# 12_-_RTC.net
KiCad netlist of a schematic drawn in Altium Designer
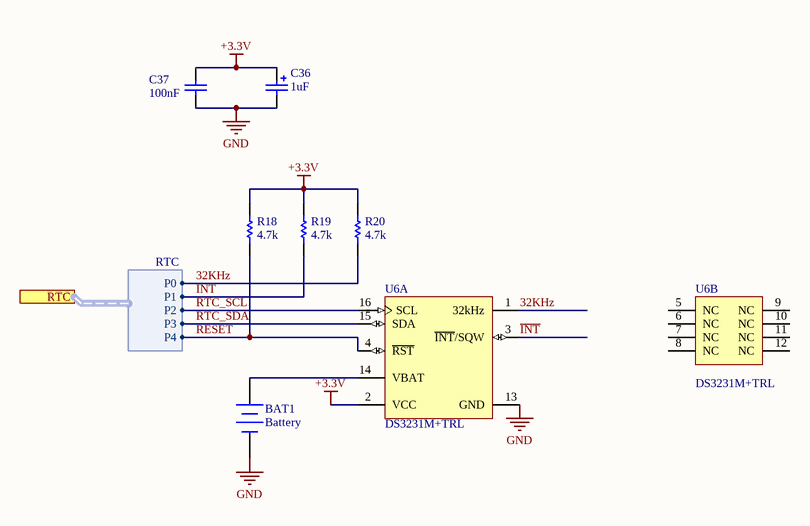
[diagram p0: [12] - RTC.SchDoc]

(export (version "E")
  (design (tool "Eeschema 10.0.6"))
  (components
    (comp (ref "BAT1")
      (value "Battery")
      (footprint "Bat")
      (description "Multicell Battery")
      (fields (field (name "PUBLISHER") "Altium Limited"))
      (libsource (lib "Miscellaneous Devices") (part "Battery"))
    )
    (comp (ref "C36")
      (value "Capacitor Polarized")
      (footprint "Tantalum 3216 A")
      (description "Aluminium SMD Capacitors")
      (fields
        (field (name "MANUFACTURER") "Panasonic")
        (field (name "MANUFACTURER PART NUMBER") "EEE-1VA331P")
        (field (name "CAPACITANCE") "1uF")
      )
      (libsource (lib "Altium_Library") (part "Capacitor Polarized"))
    )
    (comp (ref "C37")
      (value "Capacitor")
      (footprint "Cap 0603")
      (description "Chip Capacitor Nonpolar")
      (fields
        (field (name "MANUFACTURER") "Samsung")
        (field (name "MANUFACTURER PART NUMBER") "CL10B104KB8NNNC")
        (field (name "CAPACITANCE") "100nF")
      )
      (libsource (lib "Altium_Library") (part "Capacitor"))
    )
    (comp (ref "R18")
      (value "Res1")
      (footprint "Res-0603")
      (description "Chip Resistor")
      (fields
        (field (name "MANUFACTURER") "Panasonic")
        (field (name "MANUFACTURER PART NUMBER") "ERJ-3GEYJ222V")
        (field (name "RESISTANCE") "4.7k")
      )
      (libsource (lib "Altium_Library") (part "Res1"))
    )
    (comp (ref "R19")
      (value "Res1")
      (footprint "Res-0603")
      (description "Chip Resistor")
      (fields
        (field (name "MANUFACTURER") "Panasonic")
        (field (name "MANUFACTURER PART NUMBER") "ERJ-3GEYJ222V")
        (field (name "RESISTANCE") "4.7k")
      )
      (libsource (lib "Altium_Library") (part "Res1"))
    )
    (comp (ref "R20")
      (value "Res1")
      (footprint "Res-0603")
      (description "Chip Resistor")
      (fields
        (field (name "MANUFACTURER") "Panasonic")
        (field (name "MANUFACTURER PART NUMBER") "ERJ-3GEYJ222V")
        (field (name "RESISTANCE") "4.7k")
      )
      (libsource (lib "Altium_Library") (part "Res1"))
    )
    (comp (ref "U6")
      (value "DS3231M+TRL")
      (footprint "W16MK+1_N")
      (description "+/-5ppm, MEMS based Real-Time Clock, I2C Interface, 16-Pin SO, -40 to 85 degC, Pb-Free, Reel")
      (libsource (lib "Altium Content Vault") (part "PR-RTC-DS3231M-IL16"))
    )
  )
  (nets
    (net (code "2") (name "+3.3V") (class "Default")
      (node (ref "C36") (pin "1") (pinfunction "1_1") (pintype "passive"))
      (node (ref "C37") (pin "2") (pinfunction "2_2") (pintype "passive"))
      (node (ref "R18") (pin "1") (pinfunction "1_1") (pintype "passive"))
      (node (ref "R19") (pin "1") (pinfunction "1_1") (pintype "passive"))
      (node (ref "R20") (pin "1") (pinfunction "1_1") (pintype "passive"))
      (node (ref "U6") (pin "2") (pinfunction "VCC_2") (pintype "power_in"))
    )
    (net (code "3") (name "/32KHz") (class "Default")
      (node (ref "R20") (pin "2") (pinfunction "2_2") (pintype "passive"))
      (node (ref "U6") (pin "1") (pinfunction "32kHz_1") (pintype "open_collector"))
    )
    (net (code "4") (name "/RESET") (class "Default")
      (node (ref "R18") (pin "2") (pinfunction "2_2") (pintype "passive"))
      (node (ref "U6") (pin "4") (pinfunction "~{RST}_4") (pintype "bidirectional"))
    )
    (net (code "5") (name "/RTC_SCL") (class "Default")
      (node (ref "U6") (pin "16") (pinfunction "SCL_16") (pintype "input"))
    )
    (net (code "6") (name "/RTC_SDA") (class "Default")
      (node (ref "U6") (pin "15") (pinfunction "SDA_15") (pintype "bidirectional"))
    )
    (net (code "8") (name "/~{INT}") (class "Default")
      (node (ref "R19") (pin "2") (pinfunction "2_2") (pintype "passive"))
      (node (ref "U6") (pin "3") (pinfunction "~{INT}/SQW_3") (pintype "bidirectional"))
    )
    (net (code "9") (name "GND") (class "Default")
      (node (ref "BAT1") (pin "2") (pinfunction "-_2") (pintype "passive"))
      (node (ref "C36") (pin "2") (pinfunction "2_2") (pintype "passive"))
      (node (ref "C37") (pin "1") (pinfunction "1_1") (pintype "passive"))
      (node (ref "U6") (pin "13") (pinfunction "GND_13") (pintype "power_in"))
    )
    (net (code "10") (name "Net-(BAT1-+)") (class "Default")
      (node (ref "BAT1") (pin "1") (pinfunction "+_1") (pintype "passive"))
      (node (ref "U6") (pin "14") (pinfunction "VBAT_14") (pintype "power_in"))
    )
    (net (code "11") (name "unconnected-(U6B-NC-Pad5)") (class "Default")
      (node (ref "U6") (pin "5") (pinfunction "NC_5") (pintype "passive"))
    )
    (net (code "12") (name "unconnected-(U6B-NC-Pad6)") (class "Default")
      (node (ref "U6") (pin "6") (pinfunction "NC_6") (pintype "passive"))
    )
    (net (code "13") (name "unconnected-(U6B-NC-Pad7)") (class "Default")
      (node (ref "U6") (pin "7") (pinfunction "NC_7") (pintype "passive"))
    )
    (net (code "14") (name "unconnected-(U6B-NC-Pad8)") (class "Default")
      (node (ref "U6") (pin "8") (pinfunction "NC_8") (pintype "passive"))
    )
    (net (code "15") (name "unconnected-(U6B-NC-Pad9)") (class "Default")
      (node (ref "U6") (pin "9") (pinfunction "NC_9") (pintype "passive"))
    )
    (net (code "16") (name "unconnected-(U6B-NC-Pad10)") (class "Default")
      (node (ref "U6") (pin "10") (pinfunction "NC_10") (pintype "passive"))
    )
    (net (code "17") (name "unconnected-(U6B-NC-Pad11)") (class "Default")
      (node (ref "U6") (pin "11") (pinfunction "NC_11") (pintype "passive"))
    )
    (net (code "18") (name "unconnected-(U6B-NC-Pad12)") (class "Default")
      (node (ref "U6") (pin "12") (pinfunction "NC_12") (pintype "passive"))
    )
  )
)
